# ArduinoStripShield.net
KiCad netlist of a schematic drawn in EAGLE
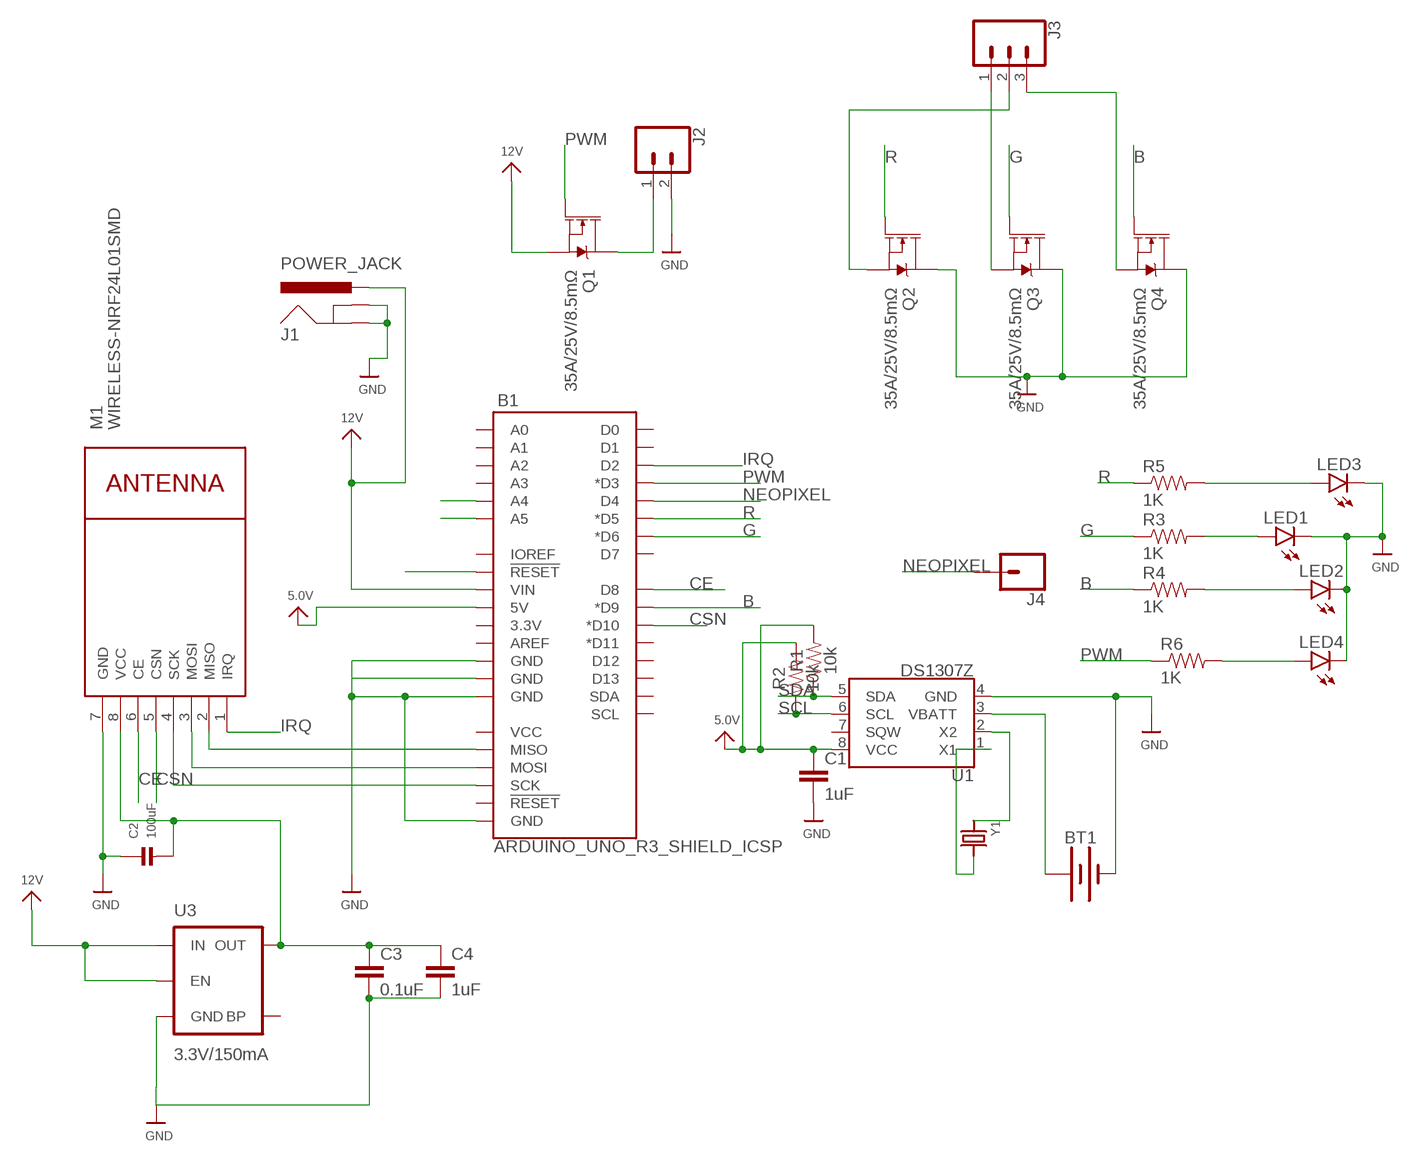
[diagram p0: schematic, sheet 1]

(export (version "E")
  (design (tool "Eeschema 10.0.6"))
  (components
    (comp (ref "B1")
      (value "ARDUINO_UNO_R3_SHIELD_ICSP")
      (footprint "eagle-import:UNO_R3_SHIELD_ICSP")
      (libsource (lib "eagle-import") (part "ARDUINO_UNO_R3_SHIELD_ICSP"))
    )
    (comp (ref "BT1")
      (value "BATTERY-12MM_SMD")
      (footprint "eagle-import:BATTCON_12MM")
      (libsource (lib "eagle-import") (part "BATTERY-12MM_SMD"))
    )
    (comp (ref "C1")
      (value "1uF")
      (footprint "eagle-import:0805")
      (libsource (lib "eagle-import") (part "CAP"))
    )
    (comp (ref "C2")
      (value "100uF")
      (footprint "eagle-import:1206")
      (libsource (lib "eagle-import") (part "CAP_CERAMIC1206"))
    )
    (comp (ref "C3")
      (value "0.1uF")
      (footprint "eagle-import:0805")
      (libsource (lib "eagle-import") (part "CAP"))
    )
    (comp (ref "C4")
      (value "1uF")
      (footprint "eagle-import:0805")
      (libsource (lib "eagle-import") (part "CAP"))
    )
    (comp (ref "J1")
      (value "POWER_JACK")
      (footprint "eagle-import:POWER_JACK_PTH")
      (libsource (lib "eagle-import") (part "POWER_JACK"))
    )
    (comp (ref "J2")
      (value "CONN_02")
      (footprint "eagle-import:1X02")
      (libsource (lib "eagle-import") (part "CONN_02"))
    )
    (comp (ref "J3")
      (value "CONN_03")
      (footprint "eagle-import:1X03")
      (libsource (lib "eagle-import") (part "CONN_03"))
    )
    (comp (ref "J4")
      (value "CONN_01")
      (footprint "eagle-import:1X01")
      (libsource (lib "eagle-import") (part "CONN_01"))
    )
    (comp (ref "LED1")
      (value "LED0603")
      (footprint "eagle-import:LED-0603")
      (libsource (lib "eagle-import") (part "LED0603"))
    )
    (comp (ref "LED2")
      (value "LED0603")
      (footprint "eagle-import:LED-0603")
      (libsource (lib "eagle-import") (part "LED0603"))
    )
    (comp (ref "LED3")
      (value "LED0603")
      (footprint "eagle-import:LED-0603")
      (libsource (lib "eagle-import") (part "LED0603"))
    )
    (comp (ref "LED4")
      (value "LED0603")
      (footprint "eagle-import:LED-0603")
      (libsource (lib "eagle-import") (part "LED0603"))
    )
    (comp (ref "M1")
      (value "WIRELESS-NRF24L01SMD")
      (footprint "eagle-import:WIRELESS-NRF24L01-SMD")
      (libsource (lib "eagle-import") (part "WIRELESS-NRF24L01SMD"))
    )
    (comp (ref "Q1")
      (value "35A/25V/8.5mΩ")
      (footprint "eagle-import:DPAK")
      (libsource (lib "eagle-import") (part "MOSFET-NCH-FDD8780"))
    )
    (comp (ref "Q2")
      (value "35A/25V/8.5mΩ")
      (footprint "eagle-import:DPAK")
      (libsource (lib "eagle-import") (part "MOSFET-NCH-FDD8780"))
    )
    (comp (ref "Q3")
      (value "35A/25V/8.5mΩ")
      (footprint "eagle-import:DPAK")
      (libsource (lib "eagle-import") (part "MOSFET-NCH-FDD8780"))
    )
    (comp (ref "Q4")
      (value "35A/25V/8.5mΩ")
      (footprint "eagle-import:DPAK")
      (libsource (lib "eagle-import") (part "MOSFET-NCH-FDD8780"))
    )
    (comp (ref "R1")
      (value "10k")
      (footprint "eagle-import:0603")
      (libsource (lib "eagle-import") (part "10KOHM-0603-1/10W-1%"))
    )
    (comp (ref "R2")
      (value "10k")
      (footprint "eagle-import:0603")
      (libsource (lib "eagle-import") (part "10KOHM-0603-1/10W-1%"))
    )
    (comp (ref "R3")
      (value "1K")
      (footprint "eagle-import:0603-RES")
      (libsource (lib "eagle-import") (part "1KOHM-1/10W-1%(0603)"))
    )
    (comp (ref "R4")
      (value "1K")
      (footprint "eagle-import:0603-RES")
      (libsource (lib "eagle-import") (part "1KOHM-1/10W-1%(0603)"))
    )
    (comp (ref "R5")
      (value "1K")
      (footprint "eagle-import:0603-RES")
      (libsource (lib "eagle-import") (part "1KOHM-1/10W-1%(0603)"))
    )
    (comp (ref "R6")
      (value "1K")
      (footprint "eagle-import:0603-RES")
      (libsource (lib "eagle-import") (part "1KOHM-1/10W-1%(0603)"))
    )
    (comp (ref "U1")
      (value "DS1307Z")
      (footprint "eagle-import:SO08-0.15")
      (libsource (lib "eagle-import") (part "DS1307Z"))
    )
    (comp (ref "U3")
      (value "3.3V/150mA")
      (footprint "eagle-import:SOT23-5")
      (libsource (lib "eagle-import") (part "V_REG_MIC52053.3V"))
    )
    (comp (ref "Y1")
      (value "CRYSTAL8X3.8SMT")
      (footprint "eagle-import:CRYSTAL_8X3.8")
      (libsource (lib "eagle-import") (part "CRYSTAL8X3.8SMT"))
    )
  )
  (nets
    (net (code "1") (name "/B") (class "Default")
      (node (ref "B1") (pin "D9") (pinfunction "*D9_D9") (pintype "bidirectional"))
      (node (ref "Q4") (pin "1") (pinfunction "G_1") (pintype "bidirectional"))
      (node (ref "R4") (pin "1") (pinfunction "1_1") (pintype "passive"))
    )
    (net (code "2") (name "/CE") (class "Default")
      (node (ref "B1") (pin "D8") (pinfunction "D8_D8") (pintype "bidirectional"))
      (node (ref "M1") (pin "6") (pinfunction "CE_6") (pintype "bidirectional"))
    )
    (net (code "3") (name "/CSN") (class "Default")
      (node (ref "B1") (pin "D10") (pinfunction "*D10_D10") (pintype "bidirectional"))
      (node (ref "M1") (pin "5") (pinfunction "CSN_5") (pintype "bidirectional"))
    )
    (net (code "4") (name "/G") (class "Default")
      (node (ref "B1") (pin "D6") (pinfunction "*D6_D6") (pintype "bidirectional"))
      (node (ref "Q3") (pin "1") (pinfunction "G_1") (pintype "bidirectional"))
      (node (ref "R3") (pin "1") (pinfunction "1_1") (pintype "passive"))
    )
    (net (code "5") (name "/IRQ") (class "Default")
      (node (ref "B1") (pin "D2") (pinfunction "D2_D2") (pintype "bidirectional"))
      (node (ref "M1") (pin "1") (pinfunction "IRQ_1") (pintype "bidirectional"))
    )
    (net (code "6") (name "/NEOPIXEL") (class "Default")
      (node (ref "B1") (pin "D4") (pinfunction "D4_D4") (pintype "bidirectional"))
      (node (ref "J4") (pin "1") (pinfunction "1_1") (pintype "passive"))
    )
    (net (code "7") (name "/PWM") (class "Default")
      (node (ref "B1") (pin "D3") (pinfunction "*D3_D3") (pintype "bidirectional"))
      (node (ref "Q1") (pin "1") (pinfunction "G_1") (pintype "bidirectional"))
      (node (ref "R6") (pin "1") (pinfunction "1_1") (pintype "passive"))
    )
    (net (code "8") (name "/R") (class "Default")
      (node (ref "B1") (pin "D5") (pinfunction "*D5_D5") (pintype "bidirectional"))
      (node (ref "Q2") (pin "1") (pinfunction "G_1") (pintype "bidirectional"))
      (node (ref "R5") (pin "1") (pinfunction "1_1") (pintype "passive"))
    )
    (net (code "9") (name "/SCL") (class "Default")
      (node (ref "B1") (pin "A5") (pinfunction "A5_A5") (pintype "bidirectional"))
      (node (ref "R2") (pin "1") (pinfunction "1_1") (pintype "passive"))
      (node (ref "U1") (pin "6") (pinfunction "SCL_6") (pintype "bidirectional"))
    )
    (net (code "10") (name "/SDA") (class "Default")
      (node (ref "B1") (pin "A4") (pinfunction "A4_A4") (pintype "bidirectional"))
      (node (ref "R1") (pin "1") (pinfunction "1_1") (pintype "passive"))
      (node (ref "U1") (pin "5") (pinfunction "SDA_5") (pintype "bidirectional"))
    )
    (net (code "11") (name "5.0V") (class "Default")
      (node (ref "B1") (pin "5V") (pinfunction "5V_5V") (pintype "bidirectional"))
      (node (ref "C1") (pin "1") (pinfunction "1_1") (pintype "passive"))
      (node (ref "R1") (pin "2") (pinfunction "2_2") (pintype "passive"))
      (node (ref "R2") (pin "2") (pinfunction "2_2") (pintype "passive"))
      (node (ref "U1") (pin "8") (pinfunction "VCC_8") (pintype "bidirectional"))
    )
    (net (code "12") (name "12V") (class "Default")
      (node (ref "B1") (pin "VIN") (pinfunction "VIN_VIN") (pintype "bidirectional"))
      (node (ref "J1") (pin "PWR") (pinfunction "PWR_PWR") (pintype "bidirectional"))
      (node (ref "Q1") (pin "3") (pinfunction "S_3") (pintype "bidirectional"))
      (node (ref "U3") (pin "1") (pinfunction "IN_1") (pintype "input"))
      (node (ref "U3") (pin "3") (pinfunction "EN_3") (pintype "input"))
    )
    (net (code "13") (name "GND") (class "Default")
      (node (ref "B1") (pin "GND@0") (pinfunction "GND_GND@0") (pintype "bidirectional"))
      (node (ref "B1") (pin "GND@1") (pinfunction "GND_GND@1") (pintype "bidirectional"))
      (node (ref "B1") (pin "GND@2") (pinfunction "GND_GND@2") (pintype "bidirectional"))
      (node (ref "B1") (pin "GND_ICSP") (pinfunction "GND_GND_ICSP") (pintype "bidirectional"))
      (node (ref "BT1") (pin "GND") (pinfunction "-_GND") (pintype "power_in"))
      (node (ref "C1") (pin "2") (pinfunction "2_2") (pintype "passive"))
      (node (ref "C2") (pin "1") (pinfunction "P$1_1") (pintype "passive"))
      (node (ref "C3") (pin "2") (pinfunction "2_2") (pintype "passive"))
      (node (ref "C4") (pin "2") (pinfunction "2_2") (pintype "passive"))
      (node (ref "J1") (pin "GND") (pinfunction "GND_GND") (pintype "bidirectional"))
      (node (ref "J1") (pin "GNDBREAK") (pinfunction "GNDBREAK_GNDBREAK") (pintype "bidirectional"))
      (node (ref "J2") (pin "2") (pinfunction "2_2") (pintype "passive"))
      (node (ref "LED1") (pin "C") (pinfunction "C_C") (pintype "passive"))
      (node (ref "LED2") (pin "C") (pinfunction "C_C") (pintype "passive"))
      (node (ref "LED3") (pin "C") (pinfunction "C_C") (pintype "passive"))
      (node (ref "LED4") (pin "C") (pinfunction "C_C") (pintype "passive"))
      (node (ref "M1") (pin "7") (pinfunction "GND_7") (pintype "power_in"))
      (node (ref "Q2") (pin "4") (pinfunction "D_4") (pintype "bidirectional"))
      (node (ref "Q3") (pin "4") (pinfunction "D_4") (pintype "bidirectional"))
      (node (ref "Q4") (pin "4") (pinfunction "D_4") (pintype "bidirectional"))
      (node (ref "U1") (pin "4") (pinfunction "GND_4") (pintype "bidirectional"))
      (node (ref "U3") (pin "2") (pinfunction "GND_2") (pintype "input"))
    )
    (net (code "14") (name "Net-(BT1-+)") (class "Default")
      (node (ref "BT1") (pin "PWR@1") (pinfunction "+_PWR@1") (pintype "power_in"))
      (node (ref "U1") (pin "3") (pinfunction "VBATT_3") (pintype "bidirectional"))
    )
    (net (code "15") (name "Net-(C2-P$2)") (class "Default")
      (node (ref "C2") (pin "2") (pinfunction "P$2_2") (pintype "passive"))
      (node (ref "C3") (pin "1") (pinfunction "1_1") (pintype "passive"))
      (node (ref "C4") (pin "1") (pinfunction "1_1") (pintype "passive"))
      (node (ref "M1") (pin "8") (pinfunction "VCC_8") (pintype "power_in"))
      (node (ref "U3") (pin "5") (pinfunction "OUT_5") (pintype "passive"))
    )
    (net (code "16") (name "Net-(LED1-PadA)") (class "Default")
      (node (ref "LED1") (pin "A") (pinfunction "A_A") (pintype "passive"))
      (node (ref "R3") (pin "2") (pinfunction "2_2") (pintype "passive"))
    )
    (net (code "17") (name "Net-(LED2-PadA)") (class "Default")
      (node (ref "LED2") (pin "A") (pinfunction "A_A") (pintype "passive"))
      (node (ref "R4") (pin "2") (pinfunction "2_2") (pintype "passive"))
    )
    (net (code "18") (name "Net-(LED3-PadA)") (class "Default")
      (node (ref "LED3") (pin "A") (pinfunction "A_A") (pintype "passive"))
      (node (ref "R5") (pin "2") (pinfunction "2_2") (pintype "passive"))
    )
    (net (code "19") (name "Net-(LED4-PadA)") (class "Default")
      (node (ref "LED4") (pin "A") (pinfunction "A_A") (pintype "passive"))
      (node (ref "R6") (pin "2") (pinfunction "2_2") (pintype "passive"))
    )
    (net (code "20") (name "Net-(M1-MISO)") (class "Default")
      (node (ref "B1") (pin "MISO") (pinfunction "MISO_MISO") (pintype "bidirectional"))
      (node (ref "M1") (pin "2") (pinfunction "MISO_2") (pintype "bidirectional"))
    )
    (net (code "21") (name "Net-(M1-MOSI)") (class "Default")
      (node (ref "B1") (pin "MOSI") (pinfunction "MOSI_MOSI") (pintype "bidirectional"))
      (node (ref "M1") (pin "3") (pinfunction "MOSI_3") (pintype "bidirectional"))
    )
    (net (code "22") (name "Net-(M1-SCK)") (class "Default")
      (node (ref "B1") (pin "SCK") (pinfunction "SCK_SCK") (pintype "bidirectional"))
      (node (ref "M1") (pin "4") (pinfunction "SCK_4") (pintype "bidirectional"))
    )
    (net (code "23") (name "Net-(Q1-D)") (class "Default")
      (node (ref "J2") (pin "1") (pinfunction "1_1") (pintype "passive"))
      (node (ref "Q1") (pin "4") (pinfunction "D_4") (pintype "bidirectional"))
    )
    (net (code "24") (name "Net-(Q2-S)") (class "Default")
      (node (ref "J3") (pin "2") (pinfunction "2_2") (pintype "passive"))
      (node (ref "Q2") (pin "3") (pinfunction "S_3") (pintype "bidirectional"))
    )
    (net (code "25") (name "Net-(Q3-S)") (class "Default")
      (node (ref "J3") (pin "1") (pinfunction "1_1") (pintype "passive"))
      (node (ref "Q3") (pin "3") (pinfunction "S_3") (pintype "bidirectional"))
    )
    (net (code "26") (name "Net-(Q4-S)") (class "Default")
      (node (ref "J3") (pin "3") (pinfunction "3_3") (pintype "passive"))
      (node (ref "Q4") (pin "3") (pinfunction "S_3") (pintype "bidirectional"))
    )
    (net (code "27") (name "Net-(U1-X1)") (class "Default")
      (node (ref "U1") (pin "1") (pinfunction "X1_1") (pintype "bidirectional"))
      (node (ref "Y1") (pin "P$4") (pinfunction "2_P$4") (pintype "passive"))
    )
    (net (code "28") (name "Net-(U1-X2)") (class "Default")
      (node (ref "U1") (pin "2") (pinfunction "X2_2") (pintype "bidirectional"))
      (node (ref "Y1") (pin "P$1") (pinfunction "1_P$1") (pintype "passive"))
    )
    (net (code "29") (name "unconnected-(B1-*D11-PadD11)") (class "Default")
      (node (ref "B1") (pin "D11") (pinfunction "*D11_D11") (pintype "bidirectional"))
    )
    (net (code "30") (name "unconnected-(B1-D0-PadRX)") (class "Default")
      (node (ref "B1") (pin "RX") (pinfunction "D0_RX") (pintype "bidirectional"))
    )
    (net (code "31") (name "unconnected-(B1-D1-PadTX)") (class "Default")
      (node (ref "B1") (pin "TX") (pinfunction "D1_TX") (pintype "bidirectional"))
    )
    (net (code "32") (name "unconnected-(B1-Pad3.3V)") (class "Default")
      (node (ref "B1") (pin "3.3V") (pinfunction "3.3V_3.3V") (pintype "bidirectional"))
    )
    (net (code "33") (name "unconnected-(B1-PadA0)") (class "Default")
      (node (ref "B1") (pin "A0") (pinfunction "A0_A0") (pintype "bidirectional"))
    )
    (net (code "34") (name "unconnected-(B1-PadA1)") (class "Default")
      (node (ref "B1") (pin "A1") (pinfunction "A1_A1") (pintype "bidirectional"))
    )
    (net (code "35") (name "unconnected-(B1-PadA2)") (class "Default")
      (node (ref "B1") (pin "A2") (pinfunction "A2_A2") (pintype "bidirectional"))
    )
    (net (code "36") (name "unconnected-(B1-PadA3)") (class "Default")
      (node (ref "B1") (pin "A3") (pinfunction "A3_A3") (pintype "bidirectional"))
    )
    (net (code "37") (name "unconnected-(B1-PadAREF)") (class "Default")
      (node (ref "B1") (pin "AREF") (pinfunction "AREF_AREF") (pintype "bidirectional"))
    )
    (net (code "38") (name "unconnected-(B1-PadD7)") (class "Default")
      (node (ref "B1") (pin "D7") (pinfunction "D7_D7") (pintype "bidirectional"))
    )
    (net (code "39") (name "unconnected-(B1-PadD12)") (class "Default")
      (node (ref "B1") (pin "D12") (pinfunction "D12_D12") (pintype "bidirectional"))
    )
    (net (code "40") (name "unconnected-(B1-PadD13)") (class "Default")
      (node (ref "B1") (pin "D13") (pinfunction "D13_D13") (pintype "bidirectional"))
    )
    (net (code "41") (name "unconnected-(B1-PadIOREF)") (class "Default")
      (node (ref "B1") (pin "IOREF") (pinfunction "IOREF_IOREF") (pintype "bidirectional"))
    )
    (net (code "42") (name "unconnected-(B1-PadSCL)") (class "Default")
      (node (ref "B1") (pin "SCL") (pinfunction "SCL_SCL") (pintype "bidirectional"))
    )
    (net (code "43") (name "unconnected-(B1-PadSDA)") (class "Default")
      (node (ref "B1") (pin "SDA") (pinfunction "SDA_SDA") (pintype "bidirectional"))
    )
    (net (code "44") (name "unconnected-(B1-VCC-Pad5V_ICSP)") (class "Default")
      (node (ref "B1") (pin "5V_ICSP") (pinfunction "VCC_5V_ICSP") (pintype "bidirectional"))
    )
    (net (code "45") (name "unconnected-(B1-~{RESET}-PadRES)") (class "Default")
      (node (ref "B1") (pin "RES") (pinfunction "~{RESET}_RES") (pintype "bidirectional"))
    )
    (net (code "46") (name "unconnected-(B1-~{RESET}-PadRST_ICSP)") (class "Default")
      (node (ref "B1") (pin "RST_ICSP") (pinfunction "~{RESET}_RST_ICSP") (pintype "bidirectional"))
    )
    (net (code "47") (name "unconnected-(U1-SQW-Pad7)") (class "Default")
      (node (ref "U1") (pin "7") (pinfunction "SQW_7") (pintype "bidirectional"))
    )
    (net (code "48") (name "unconnected-(U3-BP-Pad4)") (class "Default")
      (node (ref "U3") (pin "4") (pinfunction "BP_4") (pintype "input"))
    )
  )
)
